# Ai.net
KiCad netlist of a schematic drawn in Altium Designer
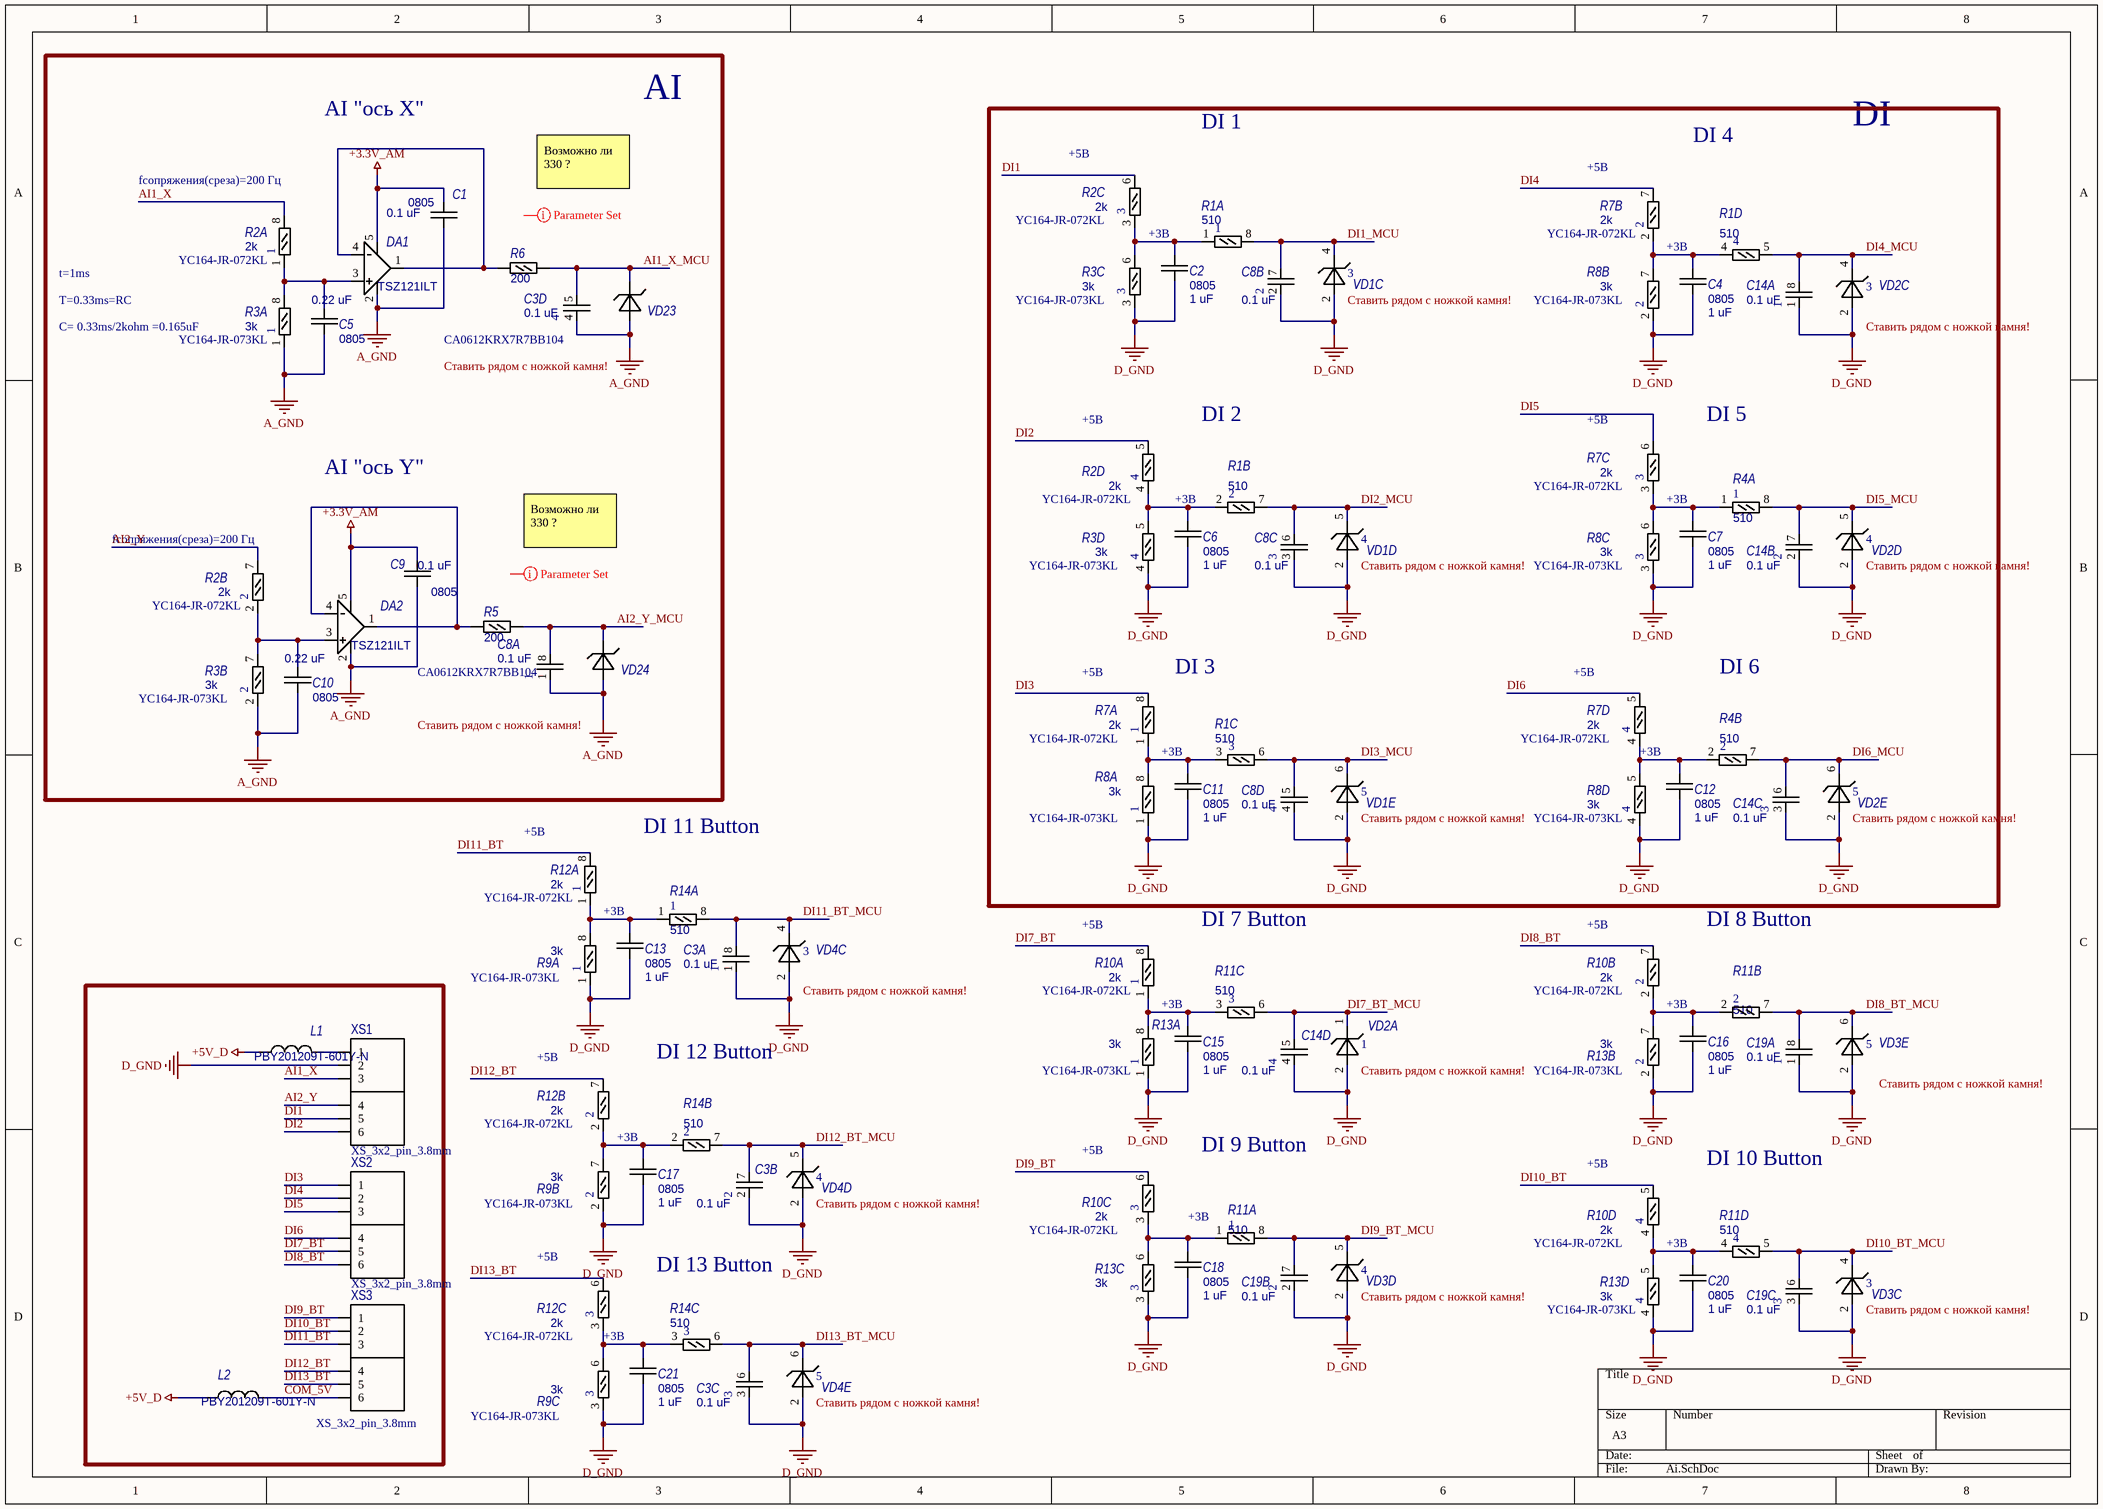
[diagram p0: Ai.SchDoc]

(export (version "E")
  (design (tool "Eeschema 10.0.6"))
  (components
    (comp (ref "C1")
      (value "0805")
      (footprint "CAP_0805_(2x1.25x1.3)")
      (description "Керамика")
      (fields (field (name "НОМИНАЛ") "0.1 uF"))
      (libsource (lib "Privod_A_K") (part "C_0805"))
    )
    (comp (ref "C2")
      (value "0805")
      (footprint "CAP_0805_(2x1.25x1.3)")
      (description "Керамика")
      (fields (field (name "НОМИНАЛ") "1 uF"))
      (libsource (lib "Privod_A_K") (part "C_0805"))
    )
    (comp (ref "C3")
      (value "Cборка 4 шт")
      (footprint "CA0612")
      (description "Capacitor 4")
      (fields (field (name "НОМИНАЛ") "0.1 uF") (field (name "ИДЕНТИФИКАТОР") "CA0612KRX7R7BB104"))
      (libsource (lib "Privod_A_K") (part "C_CA0612KRX7R7BB"))
    )
    (comp (ref "C4")
      (value "0805")
      (footprint "CAP_0805_(2x1.25x1.3)")
      (description "Керамика")
      (fields (field (name "НОМИНАЛ") "1 uF"))
      (libsource (lib "Privod_A_K") (part "C_0805"))
    )
    (comp (ref "C5")
      (value "0805")
      (footprint "CAP_0805_(2x1.25x1.3)")
      (description "Керамика")
      (fields (field (name "НОМИНАЛ") "0.22 uF"))
      (libsource (lib "Privod_A_K") (part "C_0805"))
    )
    (comp (ref "C6")
      (value "0805")
      (footprint "CAP_0805_(2x1.25x1.3)")
      (description "Керамика")
      (fields (field (name "НОМИНАЛ") "1 uF"))
      (libsource (lib "Privod_A_K") (part "C_0805"))
    )
    (comp (ref "C7")
      (value "0805")
      (footprint "CAP_0805_(2x1.25x1.3)")
      (description "Керамика")
      (fields (field (name "НОМИНАЛ") "1 uF"))
      (libsource (lib "Privod_A_K") (part "C_0805"))
    )
    (comp (ref "C8")
      (value "Cборка 4 шт")
      (footprint "CA0612")
      (description "Capacitor 4")
      (fields (field (name "НОМИНАЛ") "0.1 uF") (field (name "ИДЕНТИФИКАТОР") "CA0612KRX7R7BB104"))
      (libsource (lib "Privod_A_K") (part "C_CA0612KRX7R7BB"))
    )
    (comp (ref "C9")
      (value "0805")
      (footprint "CAP_0805_(2x1.25x1.3)")
      (description "Керамика")
      (fields (field (name "НОМИНАЛ") "0.1 uF"))
      (libsource (lib "Privod_A_K") (part "C_0805"))
    )
    (comp (ref "C10")
      (value "0805")
      (footprint "CAP_0805_(2x1.25x1.3)")
      (description "Керамика")
      (fields (field (name "НОМИНАЛ") "0.22 uF"))
      (libsource (lib "Privod_A_K") (part "C_0805"))
    )
    (comp (ref "C11")
      (value "0805")
      (footprint "CAP_0805_(2x1.25x1.3)")
      (description "Керамика")
      (fields (field (name "НОМИНАЛ") "1 uF"))
      (libsource (lib "Privod_A_K") (part "C_0805"))
    )
    (comp (ref "C12")
      (value "0805")
      (footprint "CAP_0805_(2x1.25x1.3)")
      (description "Керамика")
      (fields (field (name "НОМИНАЛ") "1 uF"))
      (libsource (lib "Privod_A_K") (part "C_0805"))
    )
    (comp (ref "C13")
      (value "0805")
      (footprint "CAP_0805_(2x1.25x1.3)")
      (description "Керамика")
      (fields (field (name "НОМИНАЛ") "1 uF"))
      (libsource (lib "Privod_A_K") (part "C_0805"))
    )
    (comp (ref "C14")
      (value "Cборка 4 шт")
      (footprint "CA0612")
      (description "Capacitor 4")
      (fields (field (name "НОМИНАЛ") "0.1 uF"))
      (libsource (lib "Privod_A_K") (part "C_CA0612KRX7R7BB"))
    )
    (comp (ref "C15")
      (value "0805")
      (footprint "CAP_0805_(2x1.25x1.3)")
      (description "Керамика")
      (fields (field (name "НОМИНАЛ") "1 uF"))
      (libsource (lib "Privod_A_K") (part "C_0805"))
    )
    (comp (ref "C16")
      (value "0805")
      (footprint "CAP_0805_(2x1.25x1.3)")
      (description "Керамика")
      (fields (field (name "НОМИНАЛ") "1 uF"))
      (libsource (lib "Privod_A_K") (part "C_0805"))
    )
    (comp (ref "C17")
      (value "0805")
      (footprint "CAP_0805_(2x1.25x1.3)")
      (description "Керамика")
      (fields (field (name "НОМИНАЛ") "1 uF"))
      (libsource (lib "Privod_A_K") (part "C_0805"))
    )
    (comp (ref "C18")
      (value "0805")
      (footprint "CAP_0805_(2x1.25x1.3)")
      (description "Керамика")
      (fields (field (name "НОМИНАЛ") "1 uF"))
      (libsource (lib "Privod_A_K") (part "C_0805"))
    )
    (comp (ref "C19")
      (value "Cборка 4 шт")
      (footprint "CA0612")
      (description "Capacitor 4")
      (fields (field (name "НОМИНАЛ") "0.1 uF"))
      (libsource (lib "Privod_A_K") (part "C_CA0612KRX7R7BB"))
    )
    (comp (ref "C20")
      (value "0805")
      (footprint "CAP_0805_(2x1.25x1.3)")
      (description "Керамика")
      (fields (field (name "НОМИНАЛ") "1 uF"))
      (libsource (lib "Privod_A_K") (part "C_0805"))
    )
    (comp (ref "C21")
      (value "0805")
      (footprint "CAP_0805_(2x1.25x1.3)")
      (description "Керамика")
      (fields (field (name "НОМИНАЛ") "1 uF"))
      (libsource (lib "Privod_A_K") (part "C_0805"))
    )
    (comp (ref "DA1")
      (value "Op Amp")
      (footprint "SOT-23-5")
      (description "Rail to Rail Op Amp")
      (fields (field (name "НАИМЕНОВАНИЕ") "TSZ121ILT"))
      (libsource (lib "Privod_A_K") (part "DA_TSZ121ILT"))
    )
    (comp (ref "DA2")
      (value "Op Amp")
      (footprint "SOT-23-5")
      (description "Rail to Rail Op Amp")
      (fields (field (name "НАИМЕНОВАНИЕ") "TSZ121ILT"))
      (libsource (lib "Privod_A_K") (part "DA_TSZ121ILT"))
    )
    (comp (ref "L1")
      (value "PBY201209T-601Y-N")
      (footprint "L_0805")
      (description "L")
      (libsource (lib "Privod_A_K") (part "L_PBY201209T-601Y-N"))
    )
    (comp (ref "L2")
      (value "PBY201209T-601Y-N")
      (footprint "L_0805")
      (description "L")
      (libsource (lib "Privod_A_K") (part "L_PBY201209T-601Y-N"))
    )
    (comp (ref "R1")
      (value "сборка 4шт")
      (footprint "YC-164")
      (description "Resistor 4")
      (fields (field (name "НОМИНАЛ") "510"))
      (libsource (lib "Privod_A_K") (part "R_YC164-JR-07"))
    )
    (comp (ref "R2")
      (value "сборка 4шт")
      (footprint "YC-164")
      (description "Resistor 4")
      (fields (field (name "НОМИНАЛ") "2k") (field (name "ИДЕНТИФИКАТОР") "YC164-JR-072KL"))
      (libsource (lib "") (part "R_YC164-JR-07_1"))
    )
    (comp (ref "R3")
      (value "сборка 4шт")
      (footprint "YC-164")
      (description "Resistor 4")
      (fields (field (name "НОМИНАЛ") "3k") (field (name "ИДЕНТИФИКАТОР") "YC164-JR-073KL"))
      (libsource (lib "") (part "R_YC164-JR-07_1"))
    )
    (comp (ref "R4")
      (value "сборка 4шт")
      (footprint "YC-164")
      (description "Resistor 4")
      (fields (field (name "НОМИНАЛ") "510"))
      (libsource (lib "Privod_A_K") (part "R_YC164-JR-07"))
    )
    (comp (ref "R5")
      (value "0805")
      (footprint "RES_0805_(2x1.2x0.45)_0.125Вт")
      (description "Resistor")
      (fields (field (name "НОМИНАЛ") "200"))
      (libsource (lib "Privod_A_K") (part "R_0805"))
    )
    (comp (ref "R6")
      (value "0805")
      (footprint "RES_0805_(2x1.2x0.45)_0.125Вт")
      (description "Resistor")
      (fields (field (name "НОМИНАЛ") "200"))
      (libsource (lib "Privod_A_K") (part "R_0805"))
    )
    (comp (ref "R7")
      (value "сборка 4шт")
      (footprint "YC-164")
      (description "Resistor 4")
      (fields (field (name "НОМИНАЛ") "2k") (field (name "ИДЕНТИФИКАТОР") "YC164-JR-072KL"))
      (libsource (lib "") (part "R_YC164-JR-07_1"))
    )
    (comp (ref "R8")
      (value "сборка 4шт")
      (footprint "YC-164")
      (description "Resistor 4")
      (fields (field (name "НОМИНАЛ") "3k") (field (name "ИДЕНТИФИКАТОР") "YC164-JR-073KL"))
      (libsource (lib "") (part "R_YC164-JR-07_1"))
    )
    (comp (ref "R9")
      (value "сборка 4шт")
      (footprint "YC-164")
      (description "Resistor 4")
      (fields (field (name "НОМИНАЛ") "3k") (field (name "ИДЕНТИФИКАТОР") "YC164-JR-073KL"))
      (libsource (lib "") (part "R_YC164-JR-07_1"))
    )
    (comp (ref "R10")
      (value "сборка 4шт")
      (footprint "YC-164")
      (description "Resistor 4")
      (fields (field (name "НОМИНАЛ") "2k") (field (name "ИДЕНТИФИКАТОР") "YC164-JR-072KL"))
      (libsource (lib "") (part "R_YC164-JR-07_1"))
    )
    (comp (ref "R11")
      (value "сборка 4шт")
      (footprint "YC-164")
      (description "Resistor 4")
      (fields (field (name "НОМИНАЛ") "510"))
      (libsource (lib "Privod_A_K") (part "R_YC164-JR-07"))
    )
    (comp (ref "R12")
      (value "сборка 4шт")
      (footprint "YC-164")
      (description "Resistor 4")
      (fields (field (name "НОМИНАЛ") "2k") (field (name "ИДЕНТИФИКАТОР") "YC164-JR-072KL"))
      (libsource (lib "") (part "R_YC164-JR-07_1"))
    )
    (comp (ref "R13")
      (value "сборка 4шт")
      (footprint "YC-164")
      (description "Resistor 4")
      (fields (field (name "НОМИНАЛ") "3k") (field (name "ИДЕНТИФИКАТОР") "YC164-JR-073KL"))
      (libsource (lib "") (part "R_YC164-JR-07_1"))
    )
    (comp (ref "R14")
      (value "сборка 4шт")
      (footprint "YC-164")
      (description "Resistor 4")
      (fields (field (name "НОМИНАЛ") "510"))
      (libsource (lib "Privod_A_K") (part "R_YC164-JR-07"))
    )
    (comp (ref "VD1")
      (value "сборка 5шт")
      (footprint "SOT-363")
      (description "Защитный диод")
      (libsource (lib "Privod_A_K") (part "VD_PESD3V3L5UY"))
    )
    (comp (ref "VD2")
      (value "сборка 5шт")
      (footprint "SOT-363")
      (description "Защитный диод")
      (libsource (lib "Privod_A_K") (part "VD_PESD3V3L5UY"))
    )
    (comp (ref "VD3")
      (value "сборка 5шт")
      (footprint "SOT-363")
      (description "Защитный диод")
      (libsource (lib "Privod_A_K") (part "VD_PESD3V3L5UY"))
    )
    (comp (ref "VD4")
      (value "сборка 5шт")
      (footprint "SOT-363")
      (description "Защитный диод")
      (libsource (lib "Privod_A_K") (part "VD_PESD3V3L5UY"))
    )
    (comp (ref "VD23")
      (value "ESD")
      (footprint "VD_SOD523")
      (description "Защитный диод")
      (libsource (lib "Privod_A_K") (part "VD_ESD"))
    )
    (comp (ref "VD24")
      (value "ESD")
      (footprint "VD_SOD523")
      (description "Защитный диод")
      (libsource (lib "Privod_A_K") (part "VD_ESD"))
    )
    (comp (ref "XS1")
      (value "XS_3x2_pin_3.8mm")
      (footprint "XS_KLS_3x2_Pin _3.8mm")
      (libsource (lib "Privod_A_K") (part "XS_3x2_pin_3.8mm"))
    )
    (comp (ref "XS2")
      (value "XS_3x2_pin_3.8mm")
      (footprint "XS_KLS_3x2_Pin _3.8mm")
      (libsource (lib "Privod_A_K") (part "XS_3x2_pin_3.8mm"))
    )
    (comp (ref "XS3")
      (value "XS_3x2_pin_3.8mm")
      (footprint "XS_KLS_3x2_Pin _3.8mm")
      (libsource (lib "Privod_A_K") (part "XS_3x2_pin_3.8mm"))
    )
  )
  (nets
    (net (code "1") (name "+3.3V_AM") (class "Default")
      (node (ref "C1") (pin "2") (pinfunction "2_2") (pintype "passive"))
      (node (ref "C9") (pin "2") (pinfunction "2_2") (pintype "passive"))
      (node (ref "DA1") (pin "5") (pinfunction "Vdd_5") (pintype "passive"))
      (node (ref "DA2") (pin "5") (pinfunction "Vdd_5") (pintype "passive"))
    )
    (net (code "2") (name "+5V_D") (class "Default")
      (node (ref "L1") (pin "1") (pinfunction "1_1") (pintype "passive"))
      (node (ref "L2") (pin "1") (pinfunction "1_1") (pintype "passive"))
    )
    (net (code "3") (name "/AI1_X") (class "Default")
      (node (ref "R2") (pin "8") (pinfunction "8_8") (pintype "passive"))
      (node (ref "XS1") (pin "3") (pinfunction "3_3") (pintype "passive"))
    )
    (net (code "4") (name "/AI1_X_MCU") (class "Default")
      (node (ref "C3") (pin "5") (pinfunction "5_5") (pintype "passive"))
      (node (ref "R6") (pin "1") (pinfunction "1_1") (pintype "passive"))
      (node (ref "VD23") (pin "2") (pinfunction "K_2") (pintype "passive"))
    )
    (net (code "5") (name "/AI2_Y") (class "Default")
      (node (ref "R2") (pin "7") (pinfunction "7_7") (pintype "passive"))
      (node (ref "XS1") (pin "4") (pinfunction "4_4") (pintype "passive"))
    )
    (net (code "6") (name "/AI2_Y_MCU") (class "Default")
      (node (ref "C8") (pin "8") (pinfunction "8_8") (pintype "passive"))
      (node (ref "R5") (pin "1") (pinfunction "1_1") (pintype "passive"))
      (node (ref "VD24") (pin "2") (pinfunction "K_2") (pintype "passive"))
    )
    (net (code "7") (name "/COM_5V") (class "Default")
      (node (ref "L2") (pin "2") (pinfunction "2_2") (pintype "passive"))
      (node (ref "XS3") (pin "6") (pinfunction "6_6") (pintype "passive"))
    )
    (net (code "8") (name "/DI1") (class "Default")
      (node (ref "R2") (pin "6") (pinfunction "6_6") (pintype "passive"))
      (node (ref "XS1") (pin "5") (pinfunction "5_5") (pintype "passive"))
    )
    (net (code "9") (name "/DI1_MCU") (class "Default")
      (node (ref "C8") (pin "7") (pinfunction "7_7") (pintype "passive"))
      (node (ref "R1") (pin "8") (pinfunction "8_8") (pintype "passive"))
      (node (ref "VD1") (pin "4") (pinfunction "K_4") (pintype "passive"))
    )
    (net (code "10") (name "/DI2") (class "Default")
      (node (ref "R2") (pin "5") (pinfunction "5_5") (pintype "passive"))
      (node (ref "XS1") (pin "6") (pinfunction "6_6") (pintype "passive"))
    )
    (net (code "11") (name "/DI2_MCU") (class "Default")
      (node (ref "C8") (pin "6") (pinfunction "6_6") (pintype "passive"))
      (node (ref "R1") (pin "7") (pinfunction "7_7") (pintype "passive"))
      (node (ref "VD1") (pin "5") (pinfunction "K_5") (pintype "passive"))
    )
    (net (code "12") (name "/DI3") (class "Default")
      (node (ref "R7") (pin "8") (pinfunction "8_8") (pintype "passive"))
      (node (ref "XS2") (pin "1") (pinfunction "1_1") (pintype "passive"))
    )
    (net (code "13") (name "/DI3_MCU") (class "Default")
      (node (ref "C8") (pin "5") (pinfunction "5_5") (pintype "passive"))
      (node (ref "R1") (pin "6") (pinfunction "6_6") (pintype "passive"))
      (node (ref "VD1") (pin "6") (pinfunction "K_6") (pintype "passive"))
    )
    (net (code "14") (name "/DI4") (class "Default")
      (node (ref "R7") (pin "7") (pinfunction "7_7") (pintype "passive"))
      (node (ref "XS2") (pin "2") (pinfunction "2_2") (pintype "passive"))
    )
    (net (code "15") (name "/DI4_MCU") (class "Default")
      (node (ref "C14") (pin "8") (pinfunction "8_8") (pintype "passive"))
      (node (ref "R1") (pin "5") (pinfunction "5_5") (pintype "passive"))
      (node (ref "VD2") (pin "4") (pinfunction "K_4") (pintype "passive"))
    )
    (net (code "16") (name "/DI5") (class "Default")
      (node (ref "R7") (pin "6") (pinfunction "6_6") (pintype "passive"))
      (node (ref "XS2") (pin "3") (pinfunction "3_3") (pintype "passive"))
    )
    (net (code "17") (name "/DI5_MCU") (class "Default")
      (node (ref "C14") (pin "7") (pinfunction "7_7") (pintype "passive"))
      (node (ref "R4") (pin "8") (pinfunction "8_8") (pintype "passive"))
      (node (ref "VD2") (pin "5") (pinfunction "K_5") (pintype "passive"))
    )
    (net (code "18") (name "/DI6") (class "Default")
      (node (ref "R7") (pin "5") (pinfunction "5_5") (pintype "passive"))
      (node (ref "XS2") (pin "4") (pinfunction "4_4") (pintype "passive"))
    )
    (net (code "19") (name "/DI6_MCU") (class "Default")
      (node (ref "C14") (pin "6") (pinfunction "6_6") (pintype "passive"))
      (node (ref "R4") (pin "7") (pinfunction "7_7") (pintype "passive"))
      (node (ref "VD2") (pin "6") (pinfunction "K_6") (pintype "passive"))
    )
    (net (code "20") (name "/DI7_BT") (class "Default")
      (node (ref "R10") (pin "8") (pinfunction "8_8") (pintype "passive"))
      (node (ref "XS2") (pin "5") (pinfunction "5_5") (pintype "passive"))
    )
    (net (code "21") (name "/DI7_BT_MCU") (class "Default")
      (node (ref "C14") (pin "5") (pinfunction "5_5") (pintype "passive"))
      (node (ref "R11") (pin "6") (pinfunction "6_6") (pintype "passive"))
      (node (ref "VD2") (pin "1") (pinfunction "K_1") (pintype "passive"))
    )
    (net (code "22") (name "/DI8_BT") (class "Default")
      (node (ref "R10") (pin "7") (pinfunction "7_7") (pintype "passive"))
      (node (ref "XS2") (pin "6") (pinfunction "6_6") (pintype "passive"))
    )
    (net (code "23") (name "/DI8_BT_MCU") (class "Default")
      (node (ref "C19") (pin "8") (pinfunction "8_8") (pintype "passive"))
      (node (ref "R11") (pin "7") (pinfunction "7_7") (pintype "passive"))
      (node (ref "VD3") (pin "6") (pinfunction "K_6") (pintype "passive"))
    )
    (net (code "24") (name "/DI9_BT") (class "Default")
      (node (ref "R10") (pin "6") (pinfunction "6_6") (pintype "passive"))
      (node (ref "XS3") (pin "1") (pinfunction "1_1") (pintype "passive"))
    )
    (net (code "25") (name "/DI9_BT_MCU") (class "Default")
      (node (ref "C19") (pin "7") (pinfunction "7_7") (pintype "passive"))
      (node (ref "R11") (pin "8") (pinfunction "8_8") (pintype "passive"))
      (node (ref "VD3") (pin "5") (pinfunction "K_5") (pintype "passive"))
    )
    (net (code "26") (name "/DI10_BT") (class "Default")
      (node (ref "R10") (pin "5") (pinfunction "5_5") (pintype "passive"))
      (node (ref "XS3") (pin "2") (pinfunction "2_2") (pintype "passive"))
    )
    (net (code "27") (name "/DI10_BT_MCU") (class "Default")
      (node (ref "C19") (pin "6") (pinfunction "6_6") (pintype "passive"))
      (node (ref "R11") (pin "5") (pinfunction "5_5") (pintype "passive"))
      (node (ref "VD3") (pin "4") (pinfunction "K_4") (pintype "passive"))
    )
    (net (code "28") (name "/DI11_BT") (class "Default")
      (node (ref "R12") (pin "8") (pinfunction "8_8") (pintype "passive"))
      (node (ref "XS3") (pin "3") (pinfunction "3_3") (pintype "passive"))
    )
    (net (code "29") (name "/DI11_BT_MCU") (class "Default")
      (node (ref "C3") (pin "8") (pinfunction "8_8") (pintype "passive"))
      (node (ref "R14") (pin "8") (pinfunction "8_8") (pintype "passive"))
      (node (ref "VD4") (pin "4") (pinfunction "K_4") (pintype "passive"))
    )
    (net (code "30") (name "/DI12_BT") (class "Default")
      (node (ref "R12") (pin "7") (pinfunction "7_7") (pintype "passive"))
      (node (ref "XS3") (pin "4") (pinfunction "4_4") (pintype "passive"))
    )
    (net (code "31") (name "/DI12_BT_MCU") (class "Default")
      (node (ref "C3") (pin "7") (pinfunction "7_7") (pintype "passive"))
      (node (ref "R14") (pin "7") (pinfunction "7_7") (pintype "passive"))
      (node (ref "VD4") (pin "5") (pinfunction "K_5") (pintype "passive"))
    )
    (net (code "32") (name "/DI13_BT") (class "Default")
      (node (ref "R12") (pin "6") (pinfunction "6_6") (pintype "passive"))
      (node (ref "XS3") (pin "5") (pinfunction "5_5") (pintype "passive"))
    )
    (net (code "33") (name "/DI13_BT_MCU") (class "Default")
      (node (ref "C3") (pin "6") (pinfunction "6_6") (pintype "passive"))
      (node (ref "R14") (pin "6") (pinfunction "6_6") (pintype "passive"))
      (node (ref "VD4") (pin "6") (pinfunction "K_6") (pintype "passive"))
    )
    (net (code "34") (name "A_GND") (class "Default")
      (node (ref "C1") (pin "1") (pinfunction "1_1") (pintype "passive"))
      (node (ref "C10") (pin "1") (pinfunction "1_1") (pintype "passive"))
      (node (ref "C3") (pin "4") (pinfunction "4_4") (pintype "passive"))
      (node (ref "C5") (pin "1") (pinfunction "1_1") (pintype "passive"))
      (node (ref "C8") (pin "1") (pinfunction "1_1") (pintype "passive"))
      (node (ref "C9") (pin "1") (pinfunction "1_1") (pintype "passive"))
      (node (ref "DA1") (pin "2") (pinfunction "Vss_2") (pintype "passive"))
      (node (ref "DA2") (pin "2") (pinfunction "Vss_2") (pintype "passive"))
      (node (ref "R3") (pin "1") (pinfunction "1_1") (pintype "passive"))
      (node (ref "R3") (pin "2") (pinfunction "2_2") (pintype "passive"))
      (node (ref "VD23") (pin "1") (pinfunction "A_1") (pintype "passive"))
      (node (ref "VD24") (pin "1") (pinfunction "A_1") (pintype "passive"))
    )
    (net (code "35") (name "D_GND") (class "Default")
      (node (ref "C11") (pin "1") (pinfunction "1_1") (pintype "passive"))
      (node (ref "C12") (pin "1") (pinfunction "1_1") (pintype "passive"))
      (node (ref "C13") (pin "1") (pinfunction "1_1") (pintype "passive"))
      (node (ref "C14") (pin "1") (pinfunction "1_1") (pintype "passive"))
      (node (ref "C14") (pin "2") (pinfunction "2_2") (pintype "passive"))
      (node (ref "C14") (pin "3") (pinfunction "3_3") (pintype "passive"))
      (node (ref "C14") (pin "4") (pinfunction "4_4") (pintype "passive"))
      (node (ref "C15") (pin "1") (pinfunction "1_1") (pintype "passive"))
      (node (ref "C16") (pin "1") (pinfunction "1_1") (pintype "passive"))
      (node (ref "C17") (pin "1") (pinfunction "1_1") (pintype "passive"))
      (node (ref "C18") (pin "1") (pinfunction "1_1") (pintype "passive"))
      (node (ref "C19") (pin "1") (pinfunction "1_1") (pintype "passive"))
      (node (ref "C19") (pin "2") (pinfunction "2_2") (pintype "passive"))
      (node (ref "C19") (pin "3") (pinfunction "3_3") (pintype "passive"))
      (node (ref "C2") (pin "1") (pinfunction "1_1") (pintype "passive"))
      (node (ref "C20") (pin "1") (pinfunction "1_1") (pintype "passive"))
      (node (ref "C21") (pin "1") (pinfunction "1_1") (pintype "passive"))
      (node (ref "C3") (pin "1") (pinfunction "1_1") (pintype "passive"))
      (node (ref "C3") (pin "2") (pinfunction "2_2") (pintype "passive"))
      (node (ref "C3") (pin "3") (pinfunction "3_3") (pintype "passive"))
      (node (ref "C4") (pin "1") (pinfunction "1_1") (pintype "passive"))
      (node (ref "C6") (pin "1") (pinfunction "1_1") (pintype "passive"))
      (node (ref "C7") (pin "1") (pinfunction "1_1") (pintype "passive"))
      (node (ref "C8") (pin "2") (pinfunction "2_2") (pintype "passive"))
      (node (ref "C8") (pin "3") (pinfunction "3_3") (pintype "passive"))
      (node (ref "C8") (pin "4") (pinfunction "4_4") (pintype "passive"))
      (node (ref "R13") (pin "1") (pinfunction "1_1") (pintype "passive"))
      (node (ref "R13") (pin "2") (pinfunction "2_2") (pintype "passive"))
      (node (ref "R13") (pin "3") (pinfunction "3_3") (pintype "passive"))
      (node (ref "R13") (pin "4") (pinfunction "4_4") (pintype "passive"))
      (node (ref "R3") (pin "3") (pinfunction "3_3") (pintype "passive"))
      (node (ref "R3") (pin "4") (pinfunction "4_4") (pintype "passive"))
      (node (ref "R8") (pin "1") (pinfunction "1_1") (pintype "passive"))
      (node (ref "R8") (pin "2") (pinfunction "2_2") (pintype "passive"))
      (node (ref "R8") (pin "3") (pinfunction "3_3") (pintype "passive"))
      (node (ref "R8") (pin "4") (pinfunction "4_4") (pintype "passive"))
      (node (ref "R9") (pin "1") (pinfunction "1_1") (pintype "passive"))
      (node (ref "R9") (pin "2") (pinfunction "2_2") (pintype "passive"))
      (node (ref "R9") (pin "3") (pinfunction "3_3") (pintype "passive"))
      (node (ref "VD1") (pin "2") (pinfunction "A_2") (pintype "passive"))
      (node (ref "VD2") (pin "2") (pinfunction "A_2") (pintype "passive"))
      (node (ref "VD3") (pin "2") (pinfunction "A_2") (pintype "passive"))
      (node (ref "VD4") (pin "2") (pinfunction "A_2") (pintype "passive"))
      (node (ref "XS1") (pin "2") (pinfunction "2_2") (pintype "passive"))
    )
    (net (code "36") (name "Net-(C2-Pad2)") (class "Default")
      (node (ref "C2") (pin "2") (pinfunction "2_2") (pintype "passive"))
      (node (ref "R1") (pin "1") (pinfunction "1_1") (pintype "passive"))
      (node (ref "R2") (pin "3") (pinfunction "3_3") (pintype "passive"))
      (node (ref "R3") (pin "6") (pinfunction "6_6") (pintype "passive"))
    )
    (net (code "37") (name "Net-(C4-Pad2)") (class "Default")
      (node (ref "C4") (pin "2") (pinfunction "2_2") (pintype "passive"))
      (node (ref "R1") (pin "4") (pinfunction "4_4") (pintype "passive"))
      (node (ref "R7") (pin "2") (pinfunction "2_2") (pintype "passive"))
      (node (ref "R8") (pin "7") (pinfunction "7_7") (pintype "passive"))
    )
    (net (code "38") (name "Net-(C6-Pad2)") (class "Default")
      (node (ref "C6") (pin "2") (pinfunction "2_2") (pintype "passive"))
      (node (ref "R1") (pin "2") (pinfunction "2_2") (pintype "passive"))
      (node (ref "R2") (pin "4") (pinfunction "4_4") (pintype "passive"))
      (node (ref "R3") (pin "5") (pinfunction "5_5") (pintype "passive"))
    )
    (net (code "39") (name "Net-(C7-Pad2)") (class "Default")
      (node (ref "C7") (pin "2") (pinfunction "2_2") (pintype "passive"))
      (node (ref "R4") (pin "1") (pinfunction "1_1") (pintype "passive"))
      (node (ref "R7") (pin "3") (pinfunction "3_3") (pintype "passive"))
      (node (ref "R8") (pin "6") (pinfunction "6_6") (pintype "passive"))
    )
    (net (code "40") (name "Net-(C11-Pad2)") (class "Default")
      (node (ref "C11") (pin "2") (pinfunction "2_2") (pintype "passive"))
      (node (ref "R1") (pin "3") (pinfunction "3_3") (pintype "passive"))
      (node (ref "R7") (pin "1") (pinfunction "1_1") (pintype "passive"))
      (node (ref "R8") (pin "8") (pinfunction "8_8") (pintype "passive"))
    )
    (net (code "41") (name "Net-(C12-Pad2)") (class "Default")
      (node (ref "C12") (pin "2") (pinfunction "2_2") (pintype "passive"))
      (node (ref "R4") (pin "2") (pinfunction "2_2") (pintype "passive"))
      (node (ref "R7") (pin "4") (pinfunction "4_4") (pintype "passive"))
      (node (ref "R8") (pin "5") (pinfunction "5_5") (pintype "passive"))
    )
    (net (code "42") (name "Net-(C13-Pad2)") (class "Default")
      (node (ref "C13") (pin "2") (pinfunction "2_2") (pintype "passive"))
      (node (ref "R12") (pin "1") (pinfunction "1_1") (pintype "passive"))
      (node (ref "R14") (pin "1") (pinfunction "1_1") (pintype "passive"))
      (node (ref "R9") (pin "8") (pinfunction "8_8") (pintype "passive"))
    )
    (net (code "43") (name "Net-(C15-Pad2)") (class "Default")
      (node (ref "C15") (pin "2") (pinfunction "2_2") (pintype "passive"))
      (node (ref "R10") (pin "1") (pinfunction "1_1") (pintype "passive"))
      (node (ref "R11") (pin "3") (pinfunction "3_3") (pintype "passive"))
      (node (ref "R13") (pin "8") (pinfunction "8_8") (pintype "passive"))
    )
    (net (code "44") (name "Net-(C16-Pad2)") (class "Default")
      (node (ref "C16") (pin "2") (pinfunction "2_2") (pintype "passive"))
      (node (ref "R10") (pin "2") (pinfunction "2_2") (pintype "passive"))
      (node (ref "R11") (pin "2") (pinfunction "2_2") (pintype "passive"))
      (node (ref "R13") (pin "7") (pinfunction "7_7") (pintype "passive"))
    )
    (net (code "45") (name "Net-(C17-Pad2)") (class "Default")
      (node (ref "C17") (pin "2") (pinfunction "2_2") (pintype "passive"))
      (node (ref "R12") (pin "2") (pinfunction "2_2") (pintype "passive"))
      (node (ref "R14") (pin "2") (pinfunction "2_2") (pintype "passive"))
      (node (ref "R9") (pin "7") (pinfunction "7_7") (pintype "passive"))
    )
    (net (code "46") (name "Net-(C18-Pad2)") (class "Default")
      (node (ref "C18") (pin "2") (pinfunction "2_2") (pintype "passive"))
      (node (ref "R10") (pin "3") (pinfunction "3_3") (pintype "passive"))
      (node (ref "R11") (pin "1") (pinfunction "1_1") (pintype "passive"))
      (node (ref "R13") (pin "6") (pinfunction "6_6") (pintype "passive"))
    )
    (net (code "47") (name "Net-(C20-Pad2)") (class "Default")
      (node (ref "C20") (pin "2") (pinfunction "2_2") (pintype "passive"))
      (node (ref "R10") (pin "4") (pinfunction "4_4") (pintype "passive"))
      (node (ref "R11") (pin "4") (pinfunction "4_4") (pintype "passive"))
      (node (ref "R13") (pin "5") (pinfunction "5_5") (pintype "passive"))
    )
    (net (code "48") (name "Net-(C21-Pad2)") (class "Default")
      (node (ref "C21") (pin "2") (pinfunction "2_2") (pintype "passive"))
      (node (ref "R12") (pin "3") (pinfunction "3_3") (pintype "passive"))
      (node (ref "R14") (pin "3") (pinfunction "3_3") (pintype "passive"))
      (node (ref "R9") (pin "6") (pinfunction "6_6") (pintype "passive"))
    )
    (net (code "49") (name "Net-(DA1-VinA+)") (class "Default")
      (node (ref "C5") (pin "2") (pinfunction "2_2") (pintype "passive"))
      (node (ref "DA1") (pin "3") (pinfunction "VinA+_3") (pintype "passive"))
      (node (ref "R2") (pin "1") (pinfunction "1_1") (pintype "passive"))
      (node (ref "R3") (pin "8") (pinfunction "8_8") (pintype "passive"))
    )
    (net (code "50") (name "Net-(DA1-VinA-)") (class "Default")
      (node (ref "DA1") (pin "1") (pinfunction "VoutA_1") (pintype "passive"))
      (node (ref "DA1") (pin "4") (pinfunction "VinA-_4") (pintype "passive"))
      (node (ref "R6") (pin "2") (pinfunction "2_2") (pintype "passive"))
    )
    (net (code "51") (name "Net-(DA2-VinA+)") (class "Default")
      (node (ref "C10") (pin "2") (pinfunction "2_2") (pintype "passive"))
      (node (ref "DA2") (pin "3") (pinfunction "VinA+_3") (pintype "passive"))
      (node (ref "R2") (pin "2") (pinfunction "2_2") (pintype "passive"))
      (node (ref "R3") (pin "7") (pinfunction "7_7") (pintype "passive"))
    )
    (net (code "52") (name "Net-(DA2-VinA-)") (class "Default")
      (node (ref "DA2") (pin "1") (pinfunction "VoutA_1") (pintype "passive"))
      (node (ref "DA2") (pin "4") (pinfunction "VinA-_4") (pintype "passive"))
      (node (ref "R5") (pin "2") (pinfunction "2_2") (pintype "passive"))
    )
    (net (code "53") (name "Net-(L1-Pad2)") (class "Default")
      (node (ref "L1") (pin "2") (pinfunction "2_2") (pintype "passive"))
      (node (ref "XS1") (pin "1") (pinfunction "1_1") (pintype "passive"))
    )
  )
)
